# mic4606_power.net
KiCad netlist of a schematic drawn in EAGLE
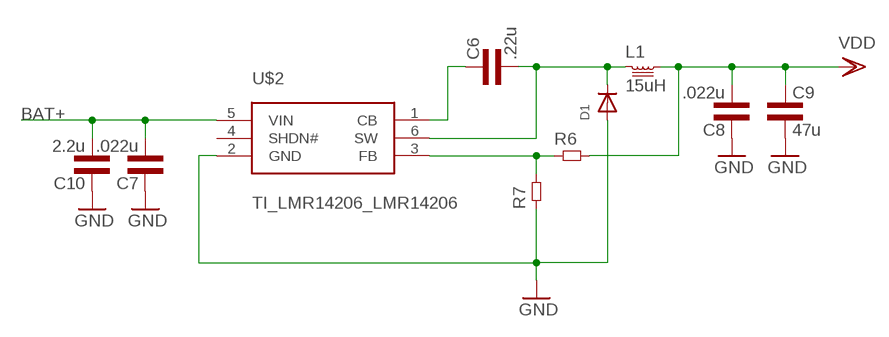
[diagram p0: schematic, sheet 1]
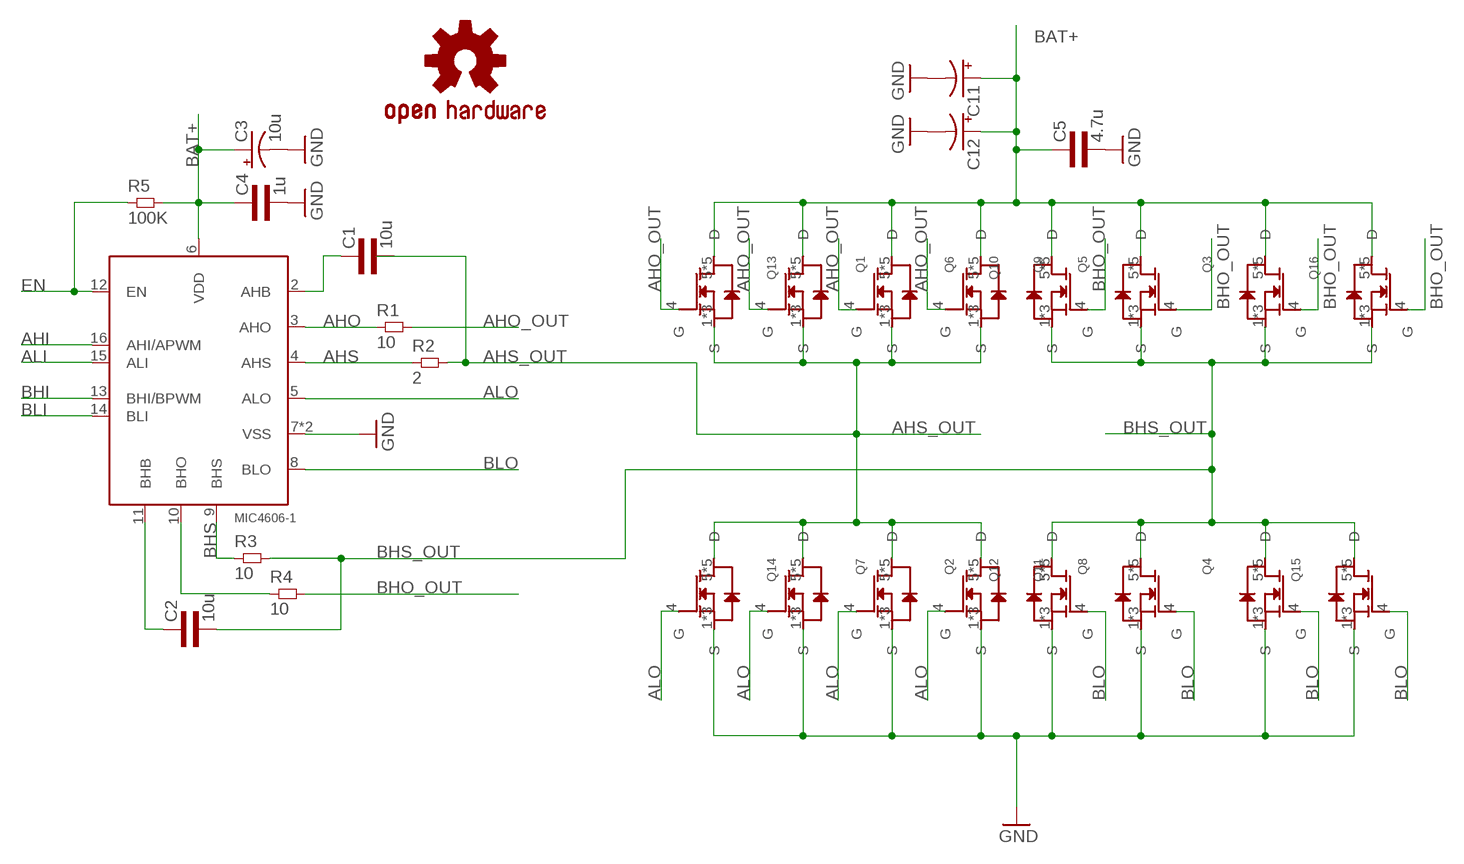
[diagram p1: schematic, sheet 2]

(export (version "E")
  (design (tool "Eeschema 10.0.6"))
  (components
    (comp (ref "C1")
      (value "10u")
      (footprint "eagle-import:0805L3")
      (libsource (lib "eagle-import") (part "CAP0805L3"))
    )
    (comp (ref "C2")
      (value "10u")
      (footprint "eagle-import:0805L3")
      (libsource (lib "eagle-import") (part "CAP0805L3"))
    )
    (comp (ref "C3")
      (value "10u")
      (footprint "eagle-import:E1,8-4")
      (libsource (lib "eagle-import") (part "CPOL-USE1.8-4"))
    )
    (comp (ref "C4")
      (value "1u")
      (footprint "eagle-import:0603L3")
      (libsource (lib "eagle-import") (part "CAP0603L3"))
    )
    (comp (ref "C5")
      (value "4.7u")
      (footprint "eagle-import:0805L3")
      (libsource (lib "eagle-import") (part "CAP0805L3"))
    )
    (comp (ref "C11")
      (value "CPOL-USF")
      (footprint "eagle-import:PANASONIC_F")
      (libsource (lib "eagle-import") (part "CPOL-USF"))
    )
    (comp (ref "C12")
      (value "CPOL-USF")
      (footprint "eagle-import:PANASONIC_F")
      (libsource (lib "eagle-import") (part "CPOL-USF"))
    )
    (comp (ref "LOGO1")
      (value "OSHW-LOGOM")
      (footprint "eagle-import:OSHW-LOGO-M")
      (libsource (lib "eagle-import") (part "OSHW-LOGOM"))
    )
    (comp (ref "MD1")
      (value "MIC4606-1")
      (footprint "eagle-import:QFN44-16LD-PL-2")
      (libsource (lib "eagle-import") (part "MIC4606-1"))
    )
    (comp (ref "Q1")
      (value "CSD18540Q5B")
      (footprint "eagle-import:Q5B")
      (libsource (lib "eagle-import") (part "CSD18540Q5B"))
    )
    (comp (ref "Q2")
      (value "CSD18540Q5B")
      (footprint "eagle-import:Q5B")
      (libsource (lib "eagle-import") (part "CSD18540Q5B"))
    )
    (comp (ref "Q3")
      (value "CSD18540Q5B")
      (footprint "eagle-import:Q5B")
      (libsource (lib "eagle-import") (part "CSD18540Q5B"))
    )
    (comp (ref "Q4")
      (value "CSD18540Q5B")
      (footprint "eagle-import:Q5B")
      (libsource (lib "eagle-import") (part "CSD18540Q5B"))
    )
    (comp (ref "Q5")
      (value "CSD18540Q5B")
      (footprint "eagle-import:Q5B")
      (libsource (lib "eagle-import") (part "CSD18540Q5B"))
    )
    (comp (ref "Q6")
      (value "CSD18540Q5B")
      (footprint "eagle-import:Q5B")
      (libsource (lib "eagle-import") (part "CSD18540Q5B"))
    )
    (comp (ref "Q7")
      (value "CSD18540Q5B")
      (footprint "eagle-import:Q5B")
      (libsource (lib "eagle-import") (part "CSD18540Q5B"))
    )
    (comp (ref "Q8")
      (value "CSD18540Q5B")
      (footprint "eagle-import:Q5B")
      (libsource (lib "eagle-import") (part "CSD18540Q5B"))
    )
    (comp (ref "Q9")
      (value "CSD18540Q5B")
      (footprint "eagle-import:Q5B")
      (libsource (lib "eagle-import") (part "CSD18540Q5B"))
    )
    (comp (ref "Q10")
      (value "CSD18540Q5B")
      (footprint "eagle-import:Q5B")
      (libsource (lib "eagle-import") (part "CSD18540Q5B"))
    )
    (comp (ref "Q11")
      (value "CSD18540Q5B")
      (footprint "eagle-import:Q5B")
      (libsource (lib "eagle-import") (part "CSD18540Q5B"))
    )
    (comp (ref "Q12")
      (value "CSD18540Q5B")
      (footprint "eagle-import:Q5B")
      (libsource (lib "eagle-import") (part "CSD18540Q5B"))
    )
    (comp (ref "Q13")
      (value "CSD18540Q5B")
      (footprint "eagle-import:Q5B")
      (libsource (lib "eagle-import") (part "CSD18540Q5B"))
    )
    (comp (ref "Q14")
      (value "CSD18540Q5B")
      (footprint "eagle-import:Q5B")
      (libsource (lib "eagle-import") (part "CSD18540Q5B"))
    )
    (comp (ref "Q15")
      (value "CSD18540Q5B")
      (footprint "eagle-import:Q5B")
      (libsource (lib "eagle-import") (part "CSD18540Q5B"))
    )
    (comp (ref "Q16")
      (value "CSD18540Q5B")
      (footprint "eagle-import:Q5B")
      (libsource (lib "eagle-import") (part "CSD18540Q5B"))
    )
    (comp (ref "R1")
      (value "10")
      (footprint "eagle-import:0805L3")
      (libsource (lib "eagle-import") (part "RES0805L3"))
    )
    (comp (ref "R2")
      (value "2")
      (footprint "eagle-import:0805L3")
      (libsource (lib "eagle-import") (part "RES0805L3"))
    )
    (comp (ref "R3")
      (value "10")
      (footprint "eagle-import:0805L3")
      (libsource (lib "eagle-import") (part "RES0805L3"))
    )
    (comp (ref "R4")
      (value "10")
      (footprint "eagle-import:0805L3")
      (libsource (lib "eagle-import") (part "RES0805L3"))
    )
    (comp (ref "R5")
      (value "100K")
      (footprint "eagle-import:0603L3")
      (libsource (lib "eagle-import") (part "RES0603L3"))
    )
    (comp (ref "C6")
      (value ".22u")
      (footprint "eagle-import:0603L3")
      (libsource (lib "eagle-import") (part "CAP0603L3"))
    )
    (comp (ref "C7")
      (value ".022u")
      (footprint "eagle-import:0603L3")
      (libsource (lib "eagle-import") (part "CAP0603L3"))
    )
    (comp (ref "C8")
      (value ".022u")
      (footprint "eagle-import:0603L3")
      (libsource (lib "eagle-import") (part "CAP0603L3"))
    )
    (comp (ref "C9")
      (value "47u")
      (footprint "eagle-import:1210L3")
      (libsource (lib "eagle-import") (part "CAP1210L3"))
    )
    (comp (ref "C10")
      (value "2.2u")
      (footprint "eagle-import:1210L3")
      (libsource (lib "eagle-import") (part "CAP1210L3"))
    )
    (comp (ref "D1")
      (value "ADAFRUIT_DIODESMA")
      (footprint "eagle-import:ADAFRUIT_SMADIODE")
      (libsource (lib "eagle-import") (part "ADAFRUIT_DIODESMA"))
    )
    (comp (ref "L1")
      (value "15uH")
      (footprint "eagle-import:NR4026")
      (libsource (lib "eagle-import") (part "NRG4026"))
    )
    (comp (ref "R6")
      (value "RES0603L3")
      (footprint "eagle-import:0603L3")
      (libsource (lib "eagle-import") (part "RES0603L3"))
    )
    (comp (ref "R7")
      (value "RES0603L3")
      (footprint "eagle-import:0603L3")
      (libsource (lib "eagle-import") (part "RES0603L3"))
    )
    (comp (ref "U$2")
      (value "TI_LMR14206_LMR14206")
      (footprint "eagle-import:TI_LMR14206_R-PDSO-G6")
      (libsource (lib "eagle-import") (part "TI_LMR14206_LMR14206"))
    )
  )
  (nets
    (net (code "1") (name "AHI") (class "Default")
      (node (ref "MD1") (pin "16") (pinfunction "AHI/APWM_16") (pintype "bidirectional"))
    )
    (net (code "2") (name "AHO") (class "Default")
      (node (ref "MD1") (pin "3") (pinfunction "AHO_3") (pintype "bidirectional"))
      (node (ref "R1") (pin "1") (pinfunction "1_1") (pintype "bidirectional"))
    )
    (net (code "3") (name "AHO_OUT") (class "Default")
      (node (ref "Q1") (pin "4") (pinfunction "G_4") (pintype "bidirectional"))
      (node (ref "Q13") (pin "4") (pinfunction "G_4") (pintype "bidirectional"))
      (node (ref "Q6") (pin "4") (pinfunction "G_4") (pintype "bidirectional"))
      (node (ref "Q9") (pin "4") (pinfunction "G_4") (pintype "bidirectional"))
      (node (ref "R1") (pin "2") (pinfunction "2_2") (pintype "bidirectional"))
    )
    (net (code "4") (name "AHS") (class "Default")
      (node (ref "MD1") (pin "4") (pinfunction "AHS_4") (pintype "bidirectional"))
      (node (ref "R2") (pin "1") (pinfunction "1_1") (pintype "bidirectional"))
    )
    (net (code "5") (name "AHS_OUT") (class "Default")
      (node (ref "C1") (pin "2") (pinfunction "2_2") (pintype "bidirectional"))
      (node (ref "Q1") (pin "1") (pinfunction "S_1") (pintype "bidirectional"))
      (node (ref "Q1") (pin "2") (pinfunction "S_2") (pintype "bidirectional"))
      (node (ref "Q1") (pin "3") (pinfunction "S_3") (pintype "bidirectional"))
      (node (ref "Q11") (pin "5") (pinfunction "D_5") (pintype "bidirectional"))
      (node (ref "Q11") (pin "6") (pinfunction "D_6") (pintype "bidirectional"))
      (node (ref "Q11") (pin "7") (pinfunction "D_7") (pintype "bidirectional"))
      (node (ref "Q11") (pin "8") (pinfunction "D_8") (pintype "bidirectional"))
      (node (ref "Q11") (pin "9") (pinfunction "D_9") (pintype "bidirectional"))
      (node (ref "Q13") (pin "1") (pinfunction "S_1") (pintype "bidirectional"))
      (node (ref "Q13") (pin "2") (pinfunction "S_2") (pintype "bidirectional"))
      (node (ref "Q13") (pin "3") (pinfunction "S_3") (pintype "bidirectional"))
      (node (ref "Q14") (pin "5") (pinfunction "D_5") (pintype "bidirectional"))
      (node (ref "Q14") (pin "6") (pinfunction "D_6") (pintype "bidirectional"))
      (node (ref "Q14") (pin "7") (pinfunction "D_7") (pintype "bidirectional"))
      (node (ref "Q14") (pin "8") (pinfunction "D_8") (pintype "bidirectional"))
      (node (ref "Q14") (pin "9") (pinfunction "D_9") (pintype "bidirectional"))
      (node (ref "Q2") (pin "5") (pinfunction "D_5") (pintype "bidirectional"))
      (node (ref "Q2") (pin "6") (pinfunction "D_6") (pintype "bidirectional"))
      (node (ref "Q2") (pin "7") (pinfunction "D_7") (pintype "bidirectional"))
      (node (ref "Q2") (pin "8") (pinfunction "D_8") (pintype "bidirectional"))
      (node (ref "Q2") (pin "9") (pinfunction "D_9") (pintype "bidirectional"))
      (node (ref "Q6") (pin "1") (pinfunction "S_1") (pintype "bidirectional"))
      (node (ref "Q6") (pin "2") (pinfunction "S_2") (pintype "bidirectional"))
      (node (ref "Q6") (pin "3") (pinfunction "S_3") (pintype "bidirectional"))
      (node (ref "Q7") (pin "5") (pinfunction "D_5") (pintype "bidirectional"))
      (node (ref "Q7") (pin "6") (pinfunction "D_6") (pintype "bidirectional"))
      (node (ref "Q7") (pin "7") (pinfunction "D_7") (pintype "bidirectional"))
      (node (ref "Q7") (pin "8") (pinfunction "D_8") (pintype "bidirectional"))
      (node (ref "Q7") (pin "9") (pinfunction "D_9") (pintype "bidirectional"))
      (node (ref "Q9") (pin "1") (pinfunction "S_1") (pintype "bidirectional"))
      (node (ref "Q9") (pin "2") (pinfunction "S_2") (pintype "bidirectional"))
      (node (ref "Q9") (pin "3") (pinfunction "S_3") (pintype "bidirectional"))
      (node (ref "R2") (pin "2") (pinfunction "2_2") (pintype "bidirectional"))
    )
    (net (code "6") (name "ALI") (class "Default")
      (node (ref "MD1") (pin "15") (pinfunction "ALI_15") (pintype "bidirectional"))
    )
    (net (code "7") (name "ALO") (class "Default")
      (node (ref "MD1") (pin "5") (pinfunction "ALO_5") (pintype "bidirectional"))
      (node (ref "Q11") (pin "4") (pinfunction "G_4") (pintype "bidirectional"))
      (node (ref "Q14") (pin "4") (pinfunction "G_4") (pintype "bidirectional"))
      (node (ref "Q2") (pin "4") (pinfunction "G_4") (pintype "bidirectional"))
      (node (ref "Q7") (pin "4") (pinfunction "G_4") (pintype "bidirectional"))
    )
    (net (code "8") (name "BAT+") (class "Default")
      (node (ref "C10") (pin "P$2") (pinfunction "2_P$2") (pintype "bidirectional"))
      (node (ref "C11") (pin "+") (pinfunction "+_+") (pintype "passive"))
      (node (ref "C12") (pin "+") (pinfunction "+_+") (pintype "passive"))
      (node (ref "C3") (pin "+") (pinfunction "+_+") (pintype "passive"))
      (node (ref "C4") (pin "P$1") (pinfunction "1_P$1") (pintype "bidirectional"))
      (node (ref "C5") (pin "1") (pinfunction "1_1") (pintype "bidirectional"))
      (node (ref "C7") (pin "P$2") (pinfunction "2_P$2") (pintype "bidirectional"))
      (node (ref "MD1") (pin "6") (pinfunction "VDD_6") (pintype "bidirectional"))
      (node (ref "Q1") (pin "5") (pinfunction "D_5") (pintype "bidirectional"))
      (node (ref "Q1") (pin "6") (pinfunction "D_6") (pintype "bidirectional"))
      (node (ref "Q1") (pin "7") (pinfunction "D_7") (pintype "bidirectional"))
      (node (ref "Q1") (pin "8") (pinfunction "D_8") (pintype "bidirectional"))
      (node (ref "Q1") (pin "9") (pinfunction "D_9") (pintype "bidirectional"))
      (node (ref "Q10") (pin "5") (pinfunction "D_5") (pintype "bidirectional"))
      (node (ref "Q10") (pin "6") (pinfunction "D_6") (pintype "bidirectional"))
      (node (ref "Q10") (pin "7") (pinfunction "D_7") (pintype "bidirectional"))
      (node (ref "Q10") (pin "8") (pinfunction "D_8") (pintype "bidirectional"))
      (node (ref "Q10") (pin "9") (pinfunction "D_9") (pintype "bidirectional"))
      (node (ref "Q13") (pin "5") (pinfunction "D_5") (pintype "bidirectional"))
      (node (ref "Q13") (pin "6") (pinfunction "D_6") (pintype "bidirectional"))
      (node (ref "Q13") (pin "7") (pinfunction "D_7") (pintype "bidirectional"))
      (node (ref "Q13") (pin "8") (pinfunction "D_8") (pintype "bidirectional"))
      (node (ref "Q13") (pin "9") (pinfunction "D_9") (pintype "bidirectional"))
      (node (ref "Q16") (pin "5") (pinfunction "D_5") (pintype "bidirectional"))
      (node (ref "Q16") (pin "6") (pinfunction "D_6") (pintype "bidirectional"))
      (node (ref "Q16") (pin "7") (pinfunction "D_7") (pintype "bidirectional"))
      (node (ref "Q16") (pin "8") (pinfunction "D_8") (pintype "bidirectional"))
      (node (ref "Q16") (pin "9") (pinfunction "D_9") (pintype "bidirectional"))
      (node (ref "Q3") (pin "5") (pinfunction "D_5") (pintype "bidirectional"))
      (node (ref "Q3") (pin "6") (pinfunction "D_6") (pintype "bidirectional"))
      (node (ref "Q3") (pin "7") (pinfunction "D_7") (pintype "bidirectional"))
      (node (ref "Q3") (pin "8") (pinfunction "D_8") (pintype "bidirectional"))
      (node (ref "Q3") (pin "9") (pinfunction "D_9") (pintype "bidirectional"))
      (node (ref "Q5") (pin "5") (pinfunction "D_5") (pintype "bidirectional"))
      (node (ref "Q5") (pin "6") (pinfunction "D_6") (pintype "bidirectional"))
      (node (ref "Q5") (pin "7") (pinfunction "D_7") (pintype "bidirectional"))
      (node (ref "Q5") (pin "8") (pinfunction "D_8") (pintype "bidirectional"))
      (node (ref "Q5") (pin "9") (pinfunction "D_9") (pintype "bidirectional"))
      (node (ref "Q6") (pin "5") (pinfunction "D_5") (pintype "bidirectional"))
      (node (ref "Q6") (pin "6") (pinfunction "D_6") (pintype "bidirectional"))
      (node (ref "Q6") (pin "7") (pinfunction "D_7") (pintype "bidirectional"))
      (node (ref "Q6") (pin "8") (pinfunction "D_8") (pintype "bidirectional"))
      (node (ref "Q6") (pin "9") (pinfunction "D_9") (pintype "bidirectional"))
      (node (ref "Q9") (pin "5") (pinfunction "D_5") (pintype "bidirectional"))
      (node (ref "Q9") (pin "6") (pinfunction "D_6") (pintype "bidirectional"))
      (node (ref "Q9") (pin "7") (pinfunction "D_7") (pintype "bidirectional"))
      (node (ref "Q9") (pin "8") (pinfunction "D_8") (pintype "bidirectional"))
      (node (ref "Q9") (pin "9") (pinfunction "D_9") (pintype "bidirectional"))
      (node (ref "R5") (pin "P$2") (pinfunction "2_P$2") (pintype "bidirectional"))
      (node (ref "U$2") (pin "5") (pinfunction "VIN_5") (pintype "bidirectional"))
    )
    (net (code "9") (name "BHI") (class "Default")
      (node (ref "MD1") (pin "13") (pinfunction "BHI/BPWM_13") (pintype "bidirectional"))
    )
    (net (code "10") (name "BHO_OUT") (class "Default")
      (node (ref "Q10") (pin "4") (pinfunction "G_4") (pintype "bidirectional"))
      (node (ref "Q16") (pin "4") (pinfunction "G_4") (pintype "bidirectional"))
      (node (ref "Q3") (pin "4") (pinfunction "G_4") (pintype "bidirectional"))
      (node (ref "Q5") (pin "4") (pinfunction "G_4") (pintype "bidirectional"))
      (node (ref "R4") (pin "2") (pinfunction "2_2") (pintype "bidirectional"))
    )
    (net (code "11") (name "BHS") (class "Default")
      (node (ref "MD1") (pin "9") (pinfunction "BHS_9") (pintype "bidirectional"))
      (node (ref "R3") (pin "1") (pinfunction "1_1") (pintype "bidirectional"))
    )
    (net (code "12") (name "BHS_OUT") (class "Default")
      (node (ref "C2") (pin "2") (pinfunction "2_2") (pintype "bidirectional"))
      (node (ref "Q10") (pin "1") (pinfunction "S_1") (pintype "bidirectional"))
      (node (ref "Q10") (pin "2") (pinfunction "S_2") (pintype "bidirectional"))
      (node (ref "Q10") (pin "3") (pinfunction "S_3") (pintype "bidirectional"))
      (node (ref "Q12") (pin "5") (pinfunction "D_5") (pintype "bidirectional"))
      (node (ref "Q12") (pin "6") (pinfunction "D_6") (pintype "bidirectional"))
      (node (ref "Q12") (pin "7") (pinfunction "D_7") (pintype "bidirectional"))
      (node (ref "Q12") (pin "8") (pinfunction "D_8") (pintype "bidirectional"))
      (node (ref "Q12") (pin "9") (pinfunction "D_9") (pintype "bidirectional"))
      (node (ref "Q15") (pin "5") (pinfunction "D_5") (pintype "bidirectional"))
      (node (ref "Q15") (pin "6") (pinfunction "D_6") (pintype "bidirectional"))
      (node (ref "Q15") (pin "7") (pinfunction "D_7") (pintype "bidirectional"))
      (node (ref "Q15") (pin "8") (pinfunction "D_8") (pintype "bidirectional"))
      (node (ref "Q15") (pin "9") (pinfunction "D_9") (pintype "bidirectional"))
      (node (ref "Q16") (pin "1") (pinfunction "S_1") (pintype "bidirectional"))
      (node (ref "Q16") (pin "2") (pinfunction "S_2") (pintype "bidirectional"))
      (node (ref "Q16") (pin "3") (pinfunction "S_3") (pintype "bidirectional"))
      (node (ref "Q3") (pin "1") (pinfunction "S_1") (pintype "bidirectional"))
      (node (ref "Q3") (pin "2") (pinfunction "S_2") (pintype "bidirectional"))
      (node (ref "Q3") (pin "3") (pinfunction "S_3") (pintype "bidirectional"))
      (node (ref "Q4") (pin "5") (pinfunction "D_5") (pintype "bidirectional"))
      (node (ref "Q4") (pin "6") (pinfunction "D_6") (pintype "bidirectional"))
      (node (ref "Q4") (pin "7") (pinfunction "D_7") (pintype "bidirectional"))
      (node (ref "Q4") (pin "8") (pinfunction "D_8") (pintype "bidirectional"))
      (node (ref "Q4") (pin "9") (pinfunction "D_9") (pintype "bidirectional"))
      (node (ref "Q5") (pin "1") (pinfunction "S_1") (pintype "bidirectional"))
      (node (ref "Q5") (pin "2") (pinfunction "S_2") (pintype "bidirectional"))
      (node (ref "Q5") (pin "3") (pinfunction "S_3") (pintype "bidirectional"))
      (node (ref "Q8") (pin "5") (pinfunction "D_5") (pintype "bidirectional"))
      (node (ref "Q8") (pin "6") (pinfunction "D_6") (pintype "bidirectional"))
      (node (ref "Q8") (pin "7") (pinfunction "D_7") (pintype "bidirectional"))
      (node (ref "Q8") (pin "8") (pinfunction "D_8") (pintype "bidirectional"))
      (node (ref "Q8") (pin "9") (pinfunction "D_9") (pintype "bidirectional"))
      (node (ref "R3") (pin "2") (pinfunction "2_2") (pintype "bidirectional"))
    )
    (net (code "13") (name "BLI") (class "Default")
      (node (ref "MD1") (pin "14") (pinfunction "BLI_14") (pintype "bidirectional"))
    )
    (net (code "14") (name "BLO") (class "Default")
      (node (ref "MD1") (pin "8") (pinfunction "BLO_8") (pintype "bidirectional"))
      (node (ref "Q12") (pin "4") (pinfunction "G_4") (pintype "bidirectional"))
      (node (ref "Q15") (pin "4") (pinfunction "G_4") (pintype "bidirectional"))
      (node (ref "Q4") (pin "4") (pinfunction "G_4") (pintype "bidirectional"))
      (node (ref "Q8") (pin "4") (pinfunction "G_4") (pintype "bidirectional"))
    )
    (net (code "15") (name "EN") (class "Default")
      (node (ref "MD1") (pin "12") (pinfunction "EN_12") (pintype "bidirectional"))
      (node (ref "R5") (pin "P$1") (pinfunction "1_P$1") (pintype "bidirectional"))
    )
    (net (code "16") (name "GND") (class "Default")
      (node (ref "C10") (pin "P$1") (pinfunction "1_P$1") (pintype "bidirectional"))
      (node (ref "C11") (pin "-") (pinfunction "-_-") (pintype "passive"))
      (node (ref "C12") (pin "-") (pinfunction "-_-") (pintype "passive"))
      (node (ref "C3") (pin "-") (pinfunction "-_-") (pintype "passive"))
      (node (ref "C4") (pin "P$2") (pinfunction "2_P$2") (pintype "bidirectional"))
      (node (ref "C5") (pin "2") (pinfunction "2_2") (pintype "bidirectional"))
      (node (ref "C7") (pin "P$1") (pinfunction "1_P$1") (pintype "bidirectional"))
      (node (ref "C8") (pin "P$1") (pinfunction "1_P$1") (pintype "bidirectional"))
      (node (ref "C9") (pin "P$2") (pinfunction "2_P$2") (pintype "bidirectional"))
      (node (ref "D1") (pin "A") (pinfunction "A_A") (pintype "passive"))
      (node (ref "MD1") (pin "7") (pinfunction "VSS_7") (pintype "bidirectional"))
      (node (ref "MD1") (pin "TP") (pinfunction "VSS_TP") (pintype "bidirectional"))
      (node (ref "Q11") (pin "1") (pinfunction "S_1") (pintype "bidirectional"))
      (node (ref "Q11") (pin "2") (pinfunction "S_2") (pintype "bidirectional"))
      (node (ref "Q11") (pin "3") (pinfunction "S_3") (pintype "bidirectional"))
      (node (ref "Q12") (pin "1") (pinfunction "S_1") (pintype "bidirectional"))
      (node (ref "Q12") (pin "2") (pinfunction "S_2") (pintype "bidirectional"))
      (node (ref "Q12") (pin "3") (pinfunction "S_3") (pintype "bidirectional"))
      (node (ref "Q14") (pin "1") (pinfunction "S_1") (pintype "bidirectional"))
      (node (ref "Q14") (pin "2") (pinfunction "S_2") (pintype "bidirectional"))
      (node (ref "Q14") (pin "3") (pinfunction "S_3") (pintype "bidirectional"))
      (node (ref "Q15") (pin "1") (pinfunction "S_1") (pintype "bidirectional"))
      (node (ref "Q15") (pin "2") (pinfunction "S_2") (pintype "bidirectional"))
      (node (ref "Q15") (pin "3") (pinfunction "S_3") (pintype "bidirectional"))
      (node (ref "Q2") (pin "1") (pinfunction "S_1") (pintype "bidirectional"))
      (node (ref "Q2") (pin "2") (pinfunction "S_2") (pintype "bidirectional"))
      (node (ref "Q2") (pin "3") (pinfunction "S_3") (pintype "bidirectional"))
      (node (ref "Q4") (pin "1") (pinfunction "S_1") (pintype "bidirectional"))
      (node (ref "Q4") (pin "2") (pinfunction "S_2") (pintype "bidirectional"))
      (node (ref "Q4") (pin "3") (pinfunction "S_3") (pintype "bidirectional"))
      (node (ref "Q7") (pin "1") (pinfunction "S_1") (pintype "bidirectional"))
      (node (ref "Q7") (pin "2") (pinfunction "S_2") (pintype "bidirectional"))
      (node (ref "Q7") (pin "3") (pinfunction "S_3") (pintype "bidirectional"))
      (node (ref "Q8") (pin "1") (pinfunction "S_1") (pintype "bidirectional"))
      (node (ref "Q8") (pin "2") (pinfunction "S_2") (pintype "bidirectional"))
      (node (ref "Q8") (pin "3") (pinfunction "S_3") (pintype "bidirectional"))
      (node (ref "R7") (pin "P$1") (pinfunction "1_P$1") (pintype "bidirectional"))
      (node (ref "U$2") (pin "2") (pinfunction "GND_2") (pintype "bidirectional"))
    )
    (net (code "17") (name "Net-(C6-1)") (class "Default")
      (node (ref "C6") (pin "P$1") (pinfunction "1_P$1") (pintype "bidirectional"))
      (node (ref "U$2") (pin "1") (pinfunction "CB_1") (pintype "bidirectional"))
    )
    (net (code "18") (name "Net-(C6-2)") (class "Default")
      (node (ref "C6") (pin "P$2") (pinfunction "2_P$2") (pintype "bidirectional"))
      (node (ref "D1") (pin "C") (pinfunction "C_C") (pintype "passive"))
      (node (ref "L1") (pin "E") (pinfunction "1_E") (pintype "bidirectional"))
      (node (ref "U$2") (pin "6") (pinfunction "SW_6") (pintype "bidirectional"))
    )
    (net (code "19") (name "Net-(MD1-AHB)") (class "Default")
      (node (ref "C1") (pin "1") (pinfunction "1_1") (pintype "bidirectional"))
      (node (ref "MD1") (pin "2") (pinfunction "AHB_2") (pintype "bidirectional"))
    )
    (net (code "20") (name "Net-(MD1-BHB)") (class "Default")
      (node (ref "C2") (pin "1") (pinfunction "1_1") (pintype "bidirectional"))
      (node (ref "MD1") (pin "11") (pinfunction "BHB_11") (pintype "bidirectional"))
    )
    (net (code "21") (name "Net-(MD1-BHO)") (class "Default")
      (node (ref "MD1") (pin "10") (pinfunction "BHO_10") (pintype "bidirectional"))
      (node (ref "R4") (pin "1") (pinfunction "1_1") (pintype "bidirectional"))
    )
    (net (code "22") (name "Net-(R6-1)") (class "Default")
      (node (ref "R6") (pin "P$1") (pinfunction "1_P$1") (pintype "bidirectional"))
      (node (ref "R7") (pin "P$2") (pinfunction "2_P$2") (pintype "bidirectional"))
      (node (ref "U$2") (pin "3") (pinfunction "FB_3") (pintype "bidirectional"))
    )
    (net (code "23") (name "VDD") (class "Default")
      (node (ref "C8") (pin "P$2") (pinfunction "2_P$2") (pintype "bidirectional"))
      (node (ref "C9") (pin "P$1") (pinfunction "1_P$1") (pintype "bidirectional"))
      (node (ref "L1") (pin "F") (pinfunction "2_F") (pintype "bidirectional"))
      (node (ref "R6") (pin "P$2") (pinfunction "2_P$2") (pintype "bidirectional"))
    )
    (net (code "24") (name "unconnected-(U$2-SHDN#-Pad4)") (class "Default")
      (node (ref "U$2") (pin "4") (pinfunction "SHDN#_4") (pintype "bidirectional"))
    )
  )
)
